# design.net
KiCad netlist of a schematic drawn in Altium Designer
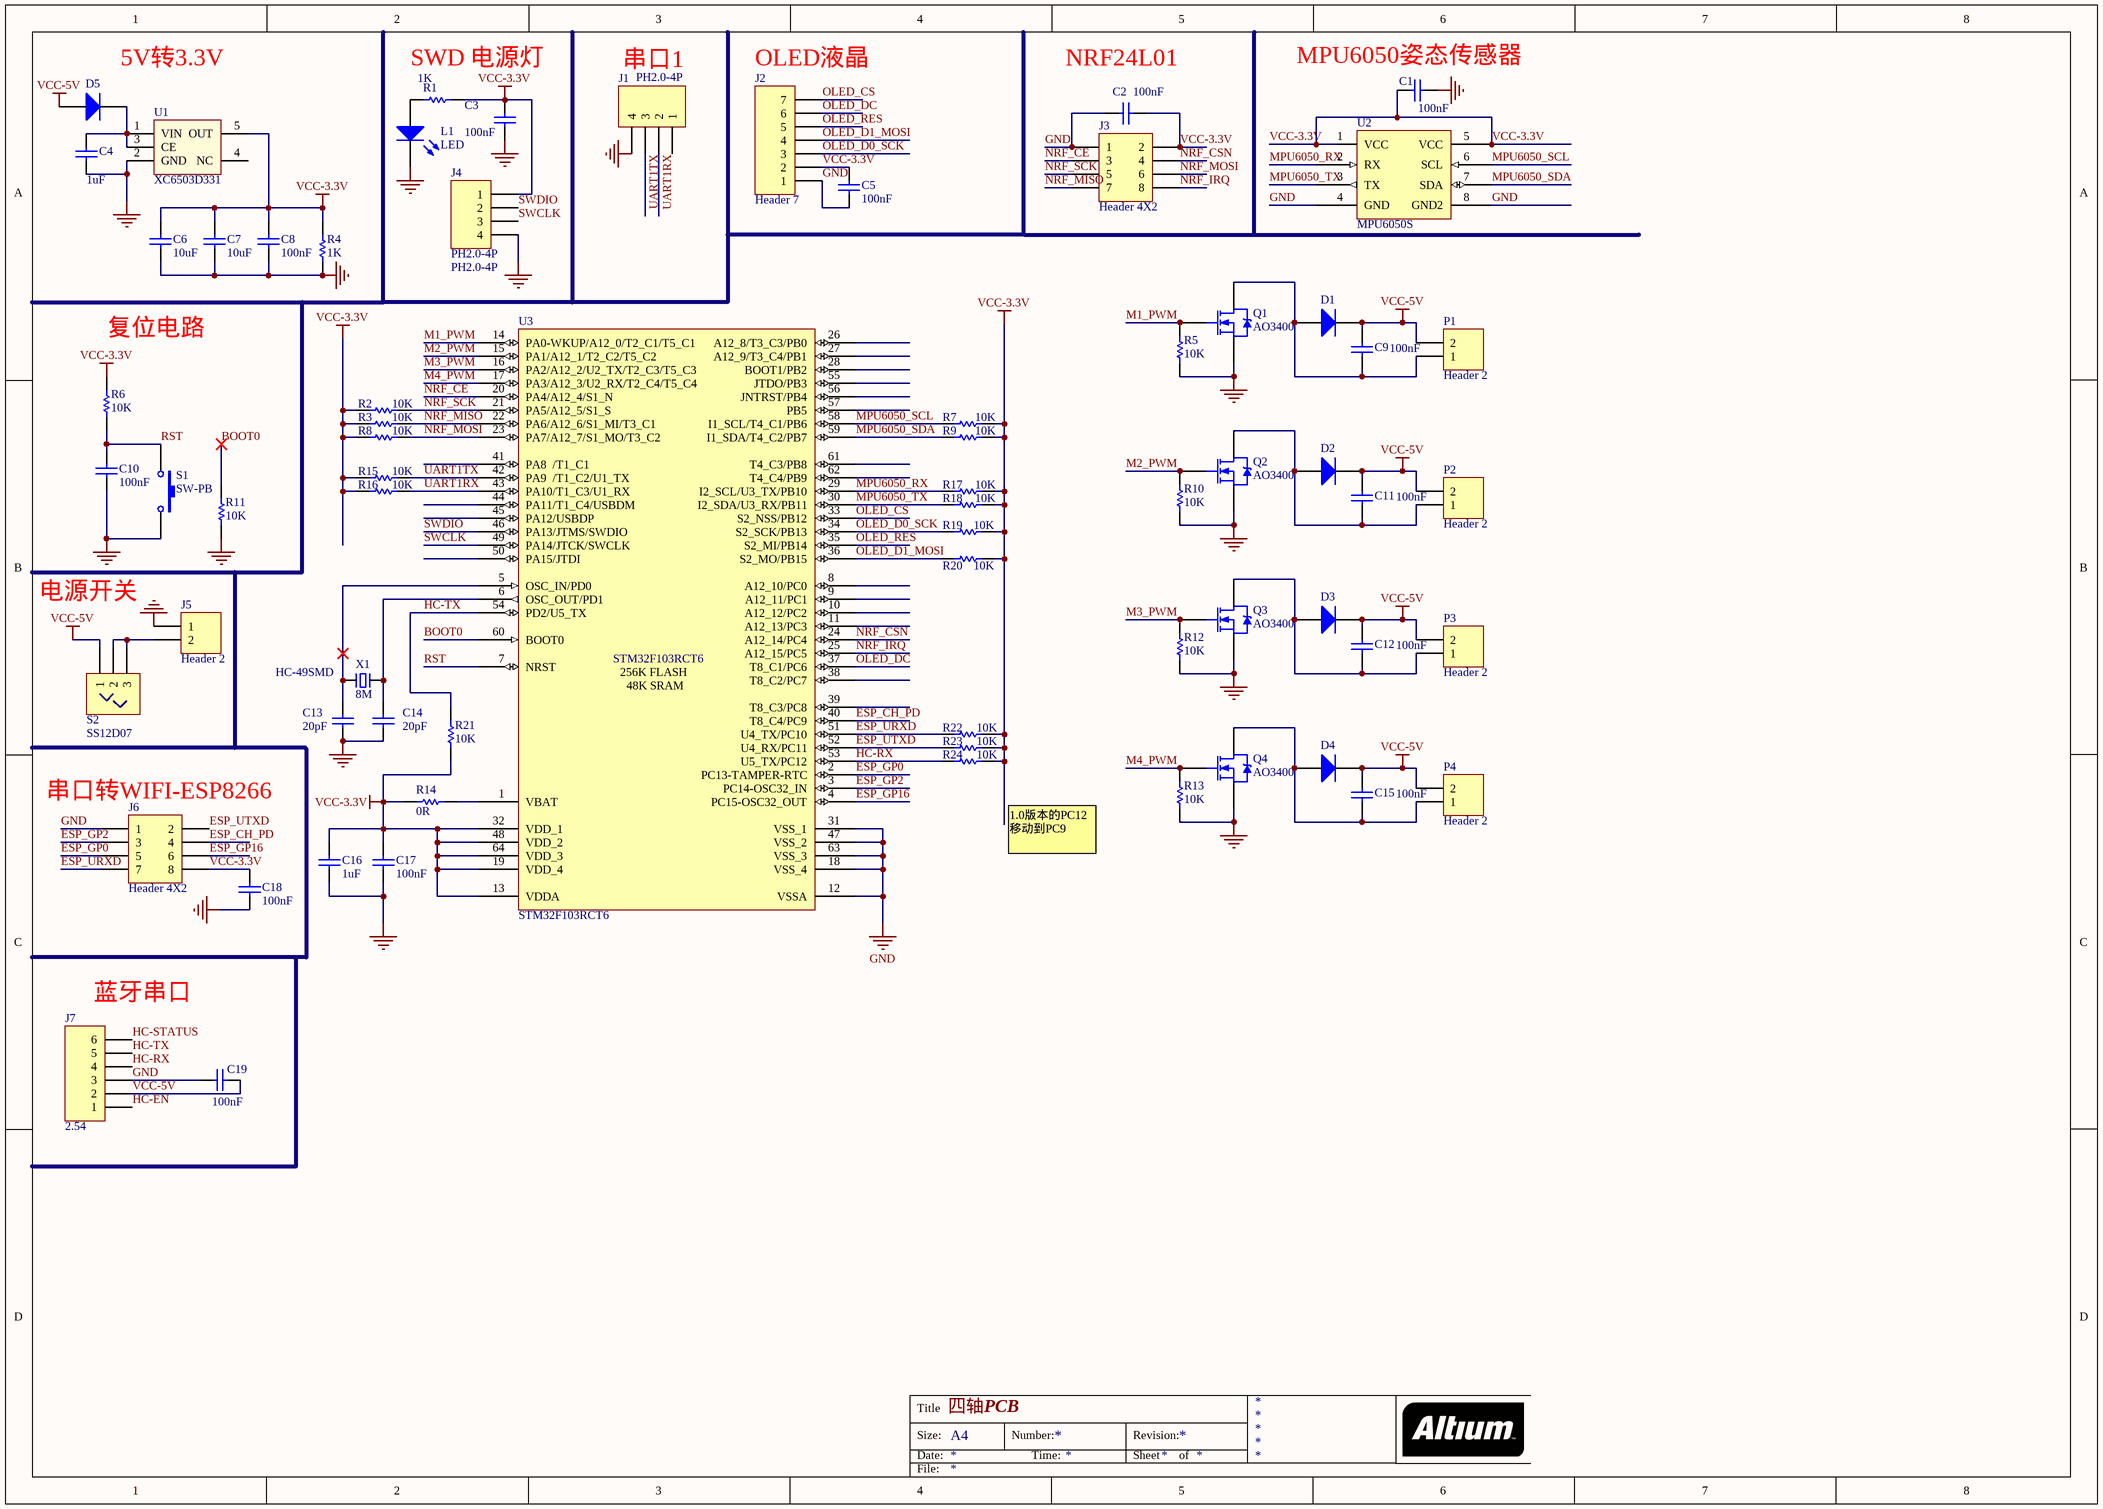
[diagram p0: 四轴.SchDoc]

(export (version "E")
  (design (tool "Eeschema 10.0.6"))
  (components
    (comp (ref "C1")
      (value "100nF")
      (footprint "LiyaoPCB库:0603")
      (description "Capacitor")
      (fields (field (name "PUBLISHER") "Altium Limited"))
      (libsource (lib "Miscellaneous Devices") (part "Cap"))
    )
    (comp (ref "C2")
      (value "100nF")
      (footprint "LiyaoPCB库:0603")
      (description "Capacitor")
      (fields (field (name "PUBLISHER") "Altium Limited"))
      (libsource (lib "Miscellaneous Devices") (part "Cap"))
    )
    (comp (ref "C3")
      (value "100nF")
      (footprint "0603")
      (description "Capacitor")
      (fields (field (name "PUBLISHER") "Altium Limited"))
      (libsource (lib "Miscellaneous Devices") (part "Cap"))
    )
    (comp (ref "C4")
      (value "1uF")
      (footprint "0603")
      (description "Capacitor")
      (fields (field (name "PUBLISHER") "Altium Limited"))
      (libsource (lib "Miscellaneous Devices") (part "Cap"))
    )
    (comp (ref "C5")
      (value "100nF")
      (footprint "LiyaoPCB库:0603")
      (description "Capacitor")
      (fields (field (name "PUBLISHER") "Altium Limited"))
      (libsource (lib "Miscellaneous Devices") (part "Cap"))
    )
    (comp (ref "C6")
      (value "10uF")
      (footprint "0603")
      (description "Capacitor")
      (fields (field (name "PUBLISHER") "Altium Limited"))
      (libsource (lib "Miscellaneous Devices") (part "Cap"))
    )
    (comp (ref "C7")
      (value "10uF")
      (footprint "0603")
      (description "Capacitor")
      (fields (field (name "PUBLISHER") "Altium Limited"))
      (libsource (lib "Miscellaneous Devices") (part "Cap"))
    )
    (comp (ref "C8")
      (value "100nF")
      (footprint "0603")
      (description "Capacitor")
      (fields (field (name "PUBLISHER") "Altium Limited"))
      (libsource (lib "Miscellaneous Devices") (part "Cap"))
    )
    (comp (ref "C9")
      (value "100nF")
      (footprint "0603")
      (description "Capacitor")
      (fields (field (name "PUBLISHER") "Altium Limited"))
      (libsource (lib "Miscellaneous Devices") (part "Cap"))
    )
    (comp (ref "C10")
      (value "100nF")
      (footprint "0603")
      (description "Capacitor")
      (fields (field (name "PUBLISHER") "Altium Limited"))
      (libsource (lib "Miscellaneous Devices") (part "Cap"))
    )
    (comp (ref "C11")
      (value "100nF")
      (footprint "0603")
      (description "Capacitor")
      (fields (field (name "PUBLISHER") "Altium Limited"))
      (libsource (lib "Miscellaneous Devices") (part "Cap"))
    )
    (comp (ref "C12")
      (value "100nF")
      (footprint "0603")
      (description "Capacitor")
      (fields (field (name "PUBLISHER") "Altium Limited"))
      (libsource (lib "Miscellaneous Devices") (part "Cap"))
    )
    (comp (ref "C13")
      (value "20pF")
      (footprint "0603")
      (description "Capacitor")
      (fields (field (name "PUBLISHER") "Altium Limited"))
      (libsource (lib "Miscellaneous Devices") (part "Cap"))
    )
    (comp (ref "C14")
      (value "20pF")
      (footprint "0603")
      (description "Capacitor")
      (fields (field (name "PUBLISHER") "Altium Limited"))
      (libsource (lib "Miscellaneous Devices") (part "Cap"))
    )
    (comp (ref "C15")
      (value "100nF")
      (footprint "0603")
      (description "Capacitor")
      (fields (field (name "PUBLISHER") "Altium Limited"))
      (libsource (lib "Miscellaneous Devices") (part "Cap"))
    )
    (comp (ref "C16")
      (value "1uF")
      (footprint "LiyaoPCB库:0603")
      (description "Capacitor")
      (fields (field (name "PUBLISHER") "Altium Limited"))
      (libsource (lib "Miscellaneous Devices") (part "Cap"))
    )
    (comp (ref "C17")
      (value "100nF")
      (footprint "LiyaoPCB库:0603")
      (description "Capacitor")
      (fields (field (name "PUBLISHER") "Altium Limited"))
      (libsource (lib "Miscellaneous Devices") (part "Cap"))
    )
    (comp (ref "C18")
      (value "100nF")
      (footprint "LiyaoPCB库:0603")
      (description "Capacitor")
      (fields (field (name "PUBLISHER") "Altium Limited"))
      (libsource (lib "Miscellaneous Devices") (part "Cap"))
    )
    (comp (ref "C19")
      (value "100nF")
      (footprint "LiyaoPCB库:0603")
      (description "Capacitor")
      (fields (field (name "PUBLISHER") "Altium Limited"))
      (libsource (lib "Miscellaneous Devices") (part "Cap"))
    )
    (comp (ref "D1")
      (value "SS14")
      (footprint "LiyaoPCB库:SMA")
      (description "28V 1A")
      (fields (field (name "PUBLISHER") "Altium Limited"))
      (libsource (lib "Liyao原理图库") (part "SS14"))
    )
    (comp (ref "D2")
      (value "SS14")
      (footprint "LiyaoPCB库:SMA")
      (description "28V 1A")
      (fields (field (name "PUBLISHER") "Altium Limited"))
      (libsource (lib "Liyao原理图库") (part "SS14"))
    )
    (comp (ref "D3")
      (value "SS14")
      (footprint "LiyaoPCB库:SMA")
      (description "28V 1A")
      (fields (field (name "PUBLISHER") "Altium Limited"))
      (libsource (lib "Liyao原理图库") (part "SS14"))
    )
    (comp (ref "D4")
      (value "SS14")
      (footprint "LiyaoPCB库:SMA")
      (description "28V 1A")
      (fields (field (name "PUBLISHER") "Altium Limited"))
      (libsource (lib "Liyao原理图库") (part "SS14"))
    )
    (comp (ref "D5")
      (value "SS14")
      (footprint "LiyaoPCB库:SMA")
      (description "28V 1A")
      (fields (field (name "PUBLISHER") "Altium Limited"))
      (libsource (lib "Liyao原理图库") (part "SS14"))
    )
    (comp (ref "J1")
      (value "PH2.0-4P")
      (footprint "PH2.0-4P")
      (description "Header, 4-Pin")
      (fields (field (name "PUBLISHER") "Altium Limited"))
      (libsource (lib "Miscellaneous Connectors") (part "Header 4"))
    )
    (comp (ref "J2")
      (value "Header 7")
      (footprint "HDR1X7")
      (description "Header, 7-Pin")
      (fields (field (name "PUBLISHER") "Altium Limited"))
      (libsource (lib "Miscellaneous Connectors") (part "Header 7"))
    )
    (comp (ref "J3")
      (value "Header 4X2")
      (footprint "HDR2X4")
      (description "Header, 4-Pin, Dual row")
      (fields (field (name "PUBLISHER") "Altium Limited"))
      (libsource (lib "Miscellaneous Connectors") (part "Header 4X2"))
    )
    (comp (ref "J4")
      (value "PH2.0-4P")
      (footprint "PH2.0-4P")
      (description "Header, 4-Pin")
      (fields (field (name "ALTIUM_VALUE") "PH2.0-4P") (field (name "PUBLISHER") "Altium Limited"))
      (libsource (lib "") (part "Header 4_1"))
    )
    (comp (ref "J5")
      (value "Header 2")
      (footprint "PH2.0-2P")
      (description "Header, 2-Pin")
      (fields (field (name "PUBLISHER") "Altium Limited"))
      (libsource (lib "Miscellaneous Connectors") (part "Header 2"))
    )
    (comp (ref "J6")
      (value "Header 4X2")
      (footprint "HDR2X4")
      (description "Header, 4-Pin, Dual row")
      (fields (field (name "PUBLISHER") "Altium Limited"))
      (libsource (lib "Miscellaneous Connectors") (part "Header 4X2"))
    )
    (comp (ref "J7")
      (value "2.54")
      (footprint "HDR1X6")
      (description "Header, 6-Pin")
      (fields (field (name "PUBLISHER") "Altium Limited"))
      (libsource (lib "Liyao端子库") (part "Header 6"))
    )
    (comp (ref "L1") (value "LED") (footprint "0603") (libsource (lib "Sparks") (part "LED")))
    (comp (ref "P1")
      (value "Header 2")
      (footprint "HDR1X2")
      (description "Header, 2-Pin")
      (fields (field (name "PUBLISHER") "Altium Limited"))
      (libsource (lib "") (part "Header 2_1"))
    )
    (comp (ref "P2")
      (value "Header 2")
      (footprint "HDR1X2")
      (description "Header, 2-Pin")
      (fields (field (name "PUBLISHER") "Altium Limited"))
      (libsource (lib "") (part "Header 2_1"))
    )
    (comp (ref "P3")
      (value "Header 2")
      (footprint "HDR1X2")
      (description "Header, 2-Pin")
      (fields (field (name "PUBLISHER") "Altium Limited"))
      (libsource (lib "") (part "Header 2_1"))
    )
    (comp (ref "P4")
      (value "Header 2")
      (footprint "HDR1X2")
      (description "Header, 2-Pin")
      (fields (field (name "PUBLISHER") "Altium Limited"))
      (libsource (lib "") (part "Header 2_1"))
    )
    (comp (ref "Q1")
      (value "AO3400")
      (footprint "SOT-23")
      (description "N-Channel MOSFET")
      (fields (field (name "PUBLISHER") "Altium Limited"))
      (libsource (lib "Liyao原理图库") (part "MOS-N"))
    )
    (comp (ref "Q2")
      (value "AO3400")
      (footprint "SOT-23")
      (description "N-Channel MOSFET")
      (fields (field (name "PUBLISHER") "Altium Limited"))
      (libsource (lib "Liyao原理图库") (part "MOS-N"))
    )
    (comp (ref "Q3")
      (value "AO3400")
      (footprint "SOT-23")
      (description "N-Channel MOSFET")
      (fields (field (name "PUBLISHER") "Altium Limited"))
      (libsource (lib "Liyao原理图库") (part "MOS-N"))
    )
    (comp (ref "Q4")
      (value "AO3400")
      (footprint "SOT-23")
      (description "N-Channel MOSFET")
      (fields (field (name "PUBLISHER") "Altium Limited"))
      (libsource (lib "Liyao原理图库") (part "MOS-N"))
    )
    (comp (ref "R1")
      (value "1K")
      (footprint "0603")
      (description "Resistor")
      (fields (field (name "PUBLISHER") "Altium Limited"))
      (libsource (lib "Miscellaneous Devices") (part "Res1"))
    )
    (comp (ref "R2")
      (value "10K")
      (footprint "C0603_M1608")
      (description "电阻0603")
      (fields (field (name "PUBLISHER") "Altium Limited"))
      (libsource (lib "Liyao原理图库") (part "Res"))
    )
    (comp (ref "R3")
      (value "10K")
      (footprint "C0603_M1608")
      (description "电阻0603")
      (fields (field (name "PUBLISHER") "Altium Limited"))
      (libsource (lib "Liyao原理图库") (part "Res"))
    )
    (comp (ref "R4")
      (value "1K")
      (footprint "0603")
      (description "Resistor")
      (fields (field (name "PUBLISHER") "Altium Limited"))
      (libsource (lib "Miscellaneous Devices") (part "Res1"))
    )
    (comp (ref "R5")
      (value "10K")
      (footprint "LiyaoPCB库:0603")
      (description "Resistor")
      (fields (field (name "PUBLISHER") "Altium Limited"))
      (libsource (lib "Miscellaneous Devices") (part "Res1"))
    )
    (comp (ref "R6")
      (value "10K")
      (footprint "0603")
      (description "Resistor")
      (fields (field (name "PUBLISHER") "Altium Limited"))
      (libsource (lib "Miscellaneous Devices") (part "Res1"))
    )
    (comp (ref "R7")
      (value "10K")
      (footprint "0603")
      (description "Resistor")
      (fields (field (name "PUBLISHER") "Altium Limited"))
      (libsource (lib "Miscellaneous Devices") (part "Res1"))
    )
    (comp (ref "R8")
      (value "10K")
      (footprint "C0603_M1608")
      (description "电阻0603")
      (fields (field (name "PUBLISHER") "Altium Limited"))
      (libsource (lib "Liyao原理图库") (part "Res"))
    )
    (comp (ref "R9")
      (value "10K")
      (footprint "0603")
      (description "Resistor")
      (fields (field (name "PUBLISHER") "Altium Limited"))
      (libsource (lib "Miscellaneous Devices") (part "Res1"))
    )
    (comp (ref "R10")
      (value "10K")
      (footprint "LiyaoPCB库:0603")
      (description "Resistor")
      (fields (field (name "PUBLISHER") "Altium Limited"))
      (libsource (lib "Miscellaneous Devices") (part "Res1"))
    )
    (comp (ref "R11")
      (value "10K")
      (footprint "0603")
      (description "Resistor")
      (fields (field (name "PUBLISHER") "Altium Limited"))
      (libsource (lib "Miscellaneous Devices") (part "Res1"))
    )
    (comp (ref "R12")
      (value "10K")
      (footprint "LiyaoPCB库:0603")
      (description "Resistor")
      (fields (field (name "PUBLISHER") "Altium Limited"))
      (libsource (lib "Miscellaneous Devices") (part "Res1"))
    )
    (comp (ref "R13")
      (value "10K")
      (footprint "LiyaoPCB库:0603")
      (description "Resistor")
      (fields (field (name "PUBLISHER") "Altium Limited"))
      (libsource (lib "Miscellaneous Devices") (part "Res1"))
    )
    (comp (ref "R14")
      (value "0R")
      (footprint "0603")
      (description "Resistor")
      (fields (field (name "PUBLISHER") "Altium Limited"))
      (libsource (lib "Miscellaneous Devices") (part "Res1"))
    )
    (comp (ref "R15")
      (value "10K")
      (footprint "C0603_M1608")
      (description "电阻0603")
      (fields (field (name "PUBLISHER") "Altium Limited"))
      (libsource (lib "Liyao原理图库") (part "Res"))
    )
    (comp (ref "R16")
      (value "10K")
      (footprint "C0603_M1608")
      (description "电阻0603")
      (fields (field (name "PUBLISHER") "Altium Limited"))
      (libsource (lib "Liyao原理图库") (part "Res"))
    )
    (comp (ref "R17")
      (value "10K")
      (footprint "C0603_M1608")
      (description "电阻0603")
      (fields (field (name "PUBLISHER") "Altium Limited"))
      (libsource (lib "Liyao原理图库") (part "Res"))
    )
    (comp (ref "R18")
      (value "10K")
      (footprint "C0603_M1608")
      (description "电阻0603")
      (fields (field (name "PUBLISHER") "Altium Limited"))
      (libsource (lib "Liyao原理图库") (part "Res"))
    )
    (comp (ref "R19")
      (value "10K")
      (footprint "C0603_M1608")
      (description "电阻0603")
      (fields (field (name "PUBLISHER") "Altium Limited"))
      (libsource (lib "Liyao原理图库") (part "Res"))
    )
    (comp (ref "R20")
      (value "10K")
      (footprint "C0603_M1608")
      (description "电阻0603")
      (fields (field (name "PUBLISHER") "Altium Limited"))
      (libsource (lib "Liyao原理图库") (part "Res"))
    )
    (comp (ref "R21")
      (value "10K")
      (footprint "C0603_M1608")
      (description "电阻0603")
      (fields (field (name "PUBLISHER") "Altium Limited"))
      (libsource (lib "Liyao原理图库") (part "Res"))
    )
    (comp (ref "R22")
      (value "10K")
      (footprint "C0603_M1608")
      (description "电阻0603")
      (fields (field (name "PUBLISHER") "Altium Limited"))
      (libsource (lib "Liyao原理图库") (part "Res"))
    )
    (comp (ref "R23")
      (value "10K")
      (footprint "C0603_M1608")
      (description "电阻0603")
      (fields (field (name "PUBLISHER") "Altium Limited"))
      (libsource (lib "Liyao原理图库") (part "Res"))
    )
    (comp (ref "R24")
      (value "10K")
      (footprint "C0603_M1608")
      (description "电阻0603")
      (fields (field (name "PUBLISHER") "Altium Limited"))
      (libsource (lib "Liyao原理图库") (part "Res"))
    )
    (comp (ref "S1")
      (value "SW-PB")
      (footprint "SW-KEY")
      (description "Switch")
      (fields (field (name "PUBLISHER") "Altium Limited"))
      (libsource (lib "Miscellaneous Devices") (part "SW-PB"))
    )
    (comp (ref "S2")
      (value "SS12D07")
      (footprint "LiyaoPCB库:SS-12D07")
      (libsource (lib "Liyao原理图库") (part "SS12D07"))
    )
    (comp (ref "U1")
      (value "XC6503D331")
      (footprint "SOT23-5")
      (libsource (lib "CYSchlib") (part "XC6503Dxxx"))
    )
    (comp (ref "U2")
      (value "MPU6050S")
      (footprint "LiyaoPCB库:MPU6050S")
      (libsource (lib "Liyao原理图库") (part "MPU6050S"))
    )
    (comp (ref "U3")
      (value "STM32F103RCT6")
      (footprint "LQFP64_N")
      (description "256K Flash 48K RAM")
      (fields (field (name "PUBLISHER") "Altium Limited"))
      (libsource (lib "Liyao原理图库") (part "STM32F103RCT6"))
    )
    (comp (ref "X1")
      (value "8M")
      (footprint "HC-49SMD")
      (fields (field (name "ALTIUM_VALUE") "HC-49SMD"))
      (libsource (lib "CYSchlib") (part "XTAL"))
    )
  )
  (nets
    (net (code "1") (name "/BOOT0") (class "Default")
      (node (ref "R11") (pin "1") (pinfunction "1_1") (pintype "passive"))
      (node (ref "U3") (pin "60") (pinfunction "BOOT0_60") (pintype "input"))
    )
    (net (code "2") (name "/ESP_CH_PD") (class "Default")
      (node (ref "J6") (pin "4") (pinfunction "4_4") (pintype "passive"))
      (node (ref "U3") (pin "40") (pinfunction "T8_C4/PC9_40") (pintype "bidirectional"))
    )
    (net (code "3") (name "/ESP_GP0") (class "Default")
      (node (ref "J6") (pin "5") (pinfunction "5_5") (pintype "passive"))
      (node (ref "U3") (pin "2") (pinfunction "PC13-TAMPER-RTC_2") (pintype "bidirectional"))
    )
    (net (code "4") (name "/ESP_GP2") (class "Default")
      (node (ref "J6") (pin "3") (pinfunction "3_3") (pintype "passive"))
      (node (ref "U3") (pin "3") (pinfunction "PC14-OSC32_IN_3") (pintype "bidirectional"))
    )
    (net (code "5") (name "/ESP_GP16") (class "Default")
      (node (ref "J6") (pin "6") (pinfunction "6_6") (pintype "passive"))
      (node (ref "U3") (pin "4") (pinfunction "PC15-OSC32_OUT_4") (pintype "bidirectional"))
    )
    (net (code "6") (name "/ESP_URXD") (class "Default")
      (node (ref "J6") (pin "7") (pinfunction "7_7") (pintype "passive"))
      (node (ref "R22") (pin "1") (pinfunction "1_1") (pintype "passive"))
      (node (ref "U3") (pin "51") (pinfunction "U4_TX/PC10_51") (pintype "bidirectional"))
    )
    (net (code "7") (name "/ESP_UTXD") (class "Default")
      (node (ref "J6") (pin "2") (pinfunction "2_2") (pintype "passive"))
      (node (ref "R23") (pin "1") (pinfunction "1_1") (pintype "passive"))
      (node (ref "U3") (pin "52") (pinfunction "U4_RX/PC11_52") (pintype "bidirectional"))
    )
    (net (code "8") (name "/HC-EN") (class "Default")
      (node (ref "J7") (pin "1") (pinfunction "1_1") (pintype "passive"))
    )
    (net (code "9") (name "/HC-RX") (class "Default")
      (node (ref "J7") (pin "4") (pinfunction "4_4") (pintype "passive"))
      (node (ref "R24") (pin "1") (pinfunction "1_1") (pintype "passive"))
      (node (ref "U3") (pin "53") (pinfunction "U5_TX/PC12_53") (pintype "bidirectional"))
    )
    (net (code "10") (name "/HC-STATUS") (class "Default")
      (node (ref "J7") (pin "6") (pinfunction "6_6") (pintype "passive"))
    )
    (net (code "11") (name "/HC-TX") (class "Default")
      (node (ref "J7") (pin "5") (pinfunction "5_5") (pintype "passive"))
      (node (ref "R21") (pin "2") (pinfunction "2_2") (pintype "passive"))
      (node (ref "U3") (pin "54") (pinfunction "PD2/U5_TX_54") (pintype "bidirectional"))
    )
    (net (code "12") (name "/M1_PWM") (class "Default")
      (node (ref "Q1") (pin "1") (pinfunction "G_1") (pintype "passive"))
      (node (ref "R5") (pin "2") (pinfunction "2_2") (pintype "passive"))
      (node (ref "U3") (pin "14") (pinfunction "PA0-WKUP/A12_0/T2_C1/T5_C1_14") (pintype "bidirectional"))
    )
    (net (code "13") (name "/M2_PWM") (class "Default")
      (node (ref "Q2") (pin "1") (pinfunction "G_1") (pintype "passive"))
      (node (ref "R10") (pin "2") (pinfunction "2_2") (pintype "passive"))
      (node (ref "U3") (pin "15") (pinfunction "PA1/A12_1/T2_C2/T5_C2_15") (pintype "bidirectional"))
    )
    (net (code "14") (name "/M3_PWM") (class "Default")
      (node (ref "Q3") (pin "1") (pinfunction "G_1") (pintype "passive"))
      (node (ref "R12") (pin "2") (pinfunction "2_2") (pintype "passive"))
      (node (ref "U3") (pin "16") (pinfunction "PA2/A12_2/U2_TX/T2_C3/T5_C3_16") (pintype "bidirectional"))
    )
    (net (code "15") (name "/M4_PWM") (class "Default")
      (node (ref "Q4") (pin "1") (pinfunction "G_1") (pintype "passive"))
      (node (ref "R13") (pin "2") (pinfunction "2_2") (pintype "passive"))
      (node (ref "U3") (pin "17") (pinfunction "PA3/A12_3/U2_RX/T2_C4/T5_C4_17") (pintype "bidirectional"))
    )
    (net (code "16") (name "/MPU6050_RX") (class "Default")
      (node (ref "R17") (pin "1") (pinfunction "1_1") (pintype "passive"))
      (node (ref "U2") (pin "2") (pinfunction "RX_2") (pintype "input"))
      (node (ref "U3") (pin "29") (pinfunction "I2_SCL/U3_TX/PB10_29") (pintype "bidirectional"))
    )
    (net (code "17") (name "/MPU6050_SCL") (class "Default")
      (node (ref "R7") (pin "2") (pinfunction "2_2") (pintype "passive"))
      (node (ref "U2") (pin "6") (pinfunction "SCL_6") (pintype "input"))
      (node (ref "U3") (pin "58") (pinfunction "I1_SCL/T4_C1/PB6_58") (pintype "bidirectional"))
    )
    (net (code "18") (name "/MPU6050_SDA") (class "Default")
      (node (ref "R9") (pin "2") (pinfunction "2_2") (pintype "passive"))
      (node (ref "U2") (pin "7") (pinfunction "SDA_7") (pintype "bidirectional"))
      (node (ref "U3") (pin "59") (pinfunction "I1_SDA/T4_C2/PB7_59") (pintype "bidirectional"))
    )
    (net (code "19") (name "/MPU6050_TX") (class "Default")
      (node (ref "R18") (pin "1") (pinfunction "1_1") (pintype "passive"))
      (node (ref "U2") (pin "3") (pinfunction "TX_3") (pintype "output"))
      (node (ref "U3") (pin "30") (pinfunction "I2_SDA/U3_RX/PB11_30") (pintype "bidirectional"))
    )
    (net (code "20") (name "/NRF_CE") (class "Default")
      (node (ref "J3") (pin "3") (pinfunction "3_3") (pintype "passive"))
      (node (ref "U3") (pin "20") (pinfunction "PA4/A12_4/S1_N_20") (pintype "bidirectional"))
    )
    (net (code "21") (name "/NRF_CSN") (class "Default")
      (node (ref "J3") (pin "4") (pinfunction "4_4") (pintype "passive"))
      (node (ref "U3") (pin "24") (pinfunction "A12_14/PC4_24") (pintype "bidirectional"))
    )
    (net (code "22") (name "/NRF_IRQ") (class "Default")
      (node (ref "J3") (pin "8") (pinfunction "8_8") (pintype "passive"))
      (node (ref "U3") (pin "25") (pinfunction "A12_15/PC5_25") (pintype "bidirectional"))
    )
    (net (code "23") (name "/NRF_MISO") (class "Default")
      (node (ref "J3") (pin "7") (pinfunction "7_7") (pintype "passive"))
      (node (ref "R3") (pin "2") (pinfunction "2_2") (pintype "passive"))
      (node (ref "U3") (pin "22") (pinfunction "PA6/A12_6/S1_MI/T3_C1_22") (pintype "bidirectional"))
    )
    (net (code "24") (name "/NRF_MOSI") (class "Default")
      (node (ref "J3") (pin "6") (pinfunction "6_6") (pintype "passive"))
      (node (ref "R8") (pin "2") (pinfunction "2_2") (pintype "passive"))
      (node (ref "U3") (pin "23") (pinfunction "PA7/A12_7/S1_MO/T3_C2_23") (pintype "bidirectional"))
    )
    (net (code "25") (name "/NRF_SCK") (class "Default")
      (node (ref "J3") (pin "5") (pinfunction "5_5") (pintype "passive"))
      (node (ref "R2") (pin "2") (pinfunction "2_2") (pintype "passive"))
      (node (ref "U3") (pin "21") (pinfunction "PA5/A12_5/S1_S_21") (pintype "bidirectional"))
    )
    (net (code "26") (name "/OLED_CS") (class "Default")
      (node (ref "J2") (pin "7") (pinfunction "7_7") (pintype "passive"))
      (node (ref "U3") (pin "33") (pinfunction "S2_NSS/PB12_33") (pintype "bidirectional"))
    )
    (net (code "27") (name "/OLED_D0_SCK") (class "Default")
      (node (ref "J2") (pin "3") (pinfunction "3_3") (pintype "passive"))
      (node (ref "R19") (pin "1") (pinfunction "1_1") (pintype "passive"))
      (node (ref "U3") (pin "34") (pinfunction "S2_SCK/PB13_34") (pintype "bidirectional"))
    )
    (net (code "28") (name "/OLED_D1_MOSI") (class "Default")
      (node (ref "J2") (pin "4") (pinfunction "4_4") (pintype "passive"))
      (node (ref "R20") (pin "1") (pinfunction "1_1") (pintype "passive"))
      (node (ref "U3") (pin "36") (pinfunction "S2_MO/PB15_36") (pintype "bidirectional"))
    )
    (net (code "29") (name "/OLED_DC") (class "Default")
      (node (ref "J2") (pin "6") (pinfunction "6_6") (pintype "passive"))
      (node (ref "U3") (pin "37") (pinfunction "T8_C1/PC6_37") (pintype "bidirectional"))
    )
    (net (code "30") (name "/OLED_RES") (class "Default")
      (node (ref "J2") (pin "5") (pinfunction "5_5") (pintype "passive"))
      (node (ref "U3") (pin "35") (pinfunction "S2_MI/PB14_35") (pintype "bidirectional"))
    )
    (net (code "31") (name "/RST") (class "Default")
      (node (ref "C10") (pin "1") (pinfunction "1_1") (pintype "passive"))
      (node (ref "R6") (pin "2") (pinfunction "2_2") (pintype "passive"))
      (node (ref "S1") (pin "1") (pinfunction "1_1") (pintype "passive"))
      (node (ref "U3") (pin "7") (pinfunction "NRST_7") (pintype "bidirectional"))
    )
    (net (code "32") (name "/SWCLK") (class "Default")
      (node (ref "J4") (pin "3") (pinfunction "3_3") (pintype "passive"))
      (node (ref "U3") (pin "49") (pinfunction "PA14/JTCK/SWCLK_49") (pintype "bidirectional"))
    )
    (net (code "33") (name "/SWDIO") (class "Default")
      (node (ref "J4") (pin "2") (pinfunction "2_2") (pintype "passive"))
      (node (ref "U3") (pin "46") (pinfunction "PA13/JTMS/SWDIO_46") (pintype "bidirectional"))
    )
    (net (code "34") (name "/UART1RX") (class "Default")
      (node (ref "J1") (pin "2") (pinfunction "2_2") (pintype "passive"))
      (node (ref "R16") (pin "2") (pinfunction "2_2") (pintype "passive"))
      (node (ref "U3") (pin "43") (pinfunction "PA10/T1_C3/U1_RX_43") (pintype "bidirectional"))
    )
    (net (code "35") (name "/UART1TX") (class "Default")
      (node (ref "J1") (pin "3") (pinfunction "3_3") (pintype "passive"))
      (node (ref "R15") (pin "2") (pinfunction "2_2") (pintype "passive"))
      (node (ref "U3") (pin "42") (pinfunction "PA9__/T1_C2/U1_TX_42") (pintype "bidirectional"))
    )
    (net (code "36") (name "GND") (class "Default")
      (node (ref "C1") (pin "2") (pinfunction "2_2") (pintype "passive"))
      (node (ref "C10") (pin "2") (pinfunction "2_2") (pintype "passive"))
      (node (ref "C13") (pin "1") (pinfunction "1_1") (pintype "passive"))
      (node (ref "C14") (pin "1") (pinfunction "1_1") (pintype "passive"))
      (node (ref "C16") (pin "1") (pinfunction "1_1") (pintype "passive"))
      (node (ref "C17") (pin "1") (pinfunction "1_1") (pintype "passive"))
      (node (ref "C18") (pin "2") (pinfunction "2_2") (pintype "passive"))
      (node (ref "C19") (pin "1") (pinfunction "1_1") (pintype "passive"))
      (node (ref "C2") (pin "2") (pinfunction "2_2") (pintype "passive"))
      (node (ref "C3") (pin "2") (pinfunction "2_2") (pintype "passive"))
      (node (ref "C4") (pin "1") (pinfunction "1_1") (pintype "passive"))
      (node (ref "C5") (pin "2") (pinfunction "2_2") (pintype "passive"))
      (node (ref "C6") (pin "2") (pinfunction "2_2") (pintype "passive"))
      (node (ref "C7") (pin "1") (pinfunction "1_1") (pintype "passive"))
      (node (ref "C8") (pin "1") (pinfunction "1_1") (pintype "passive"))
      (node (ref "J1") (pin "4") (pinfunction "4_4") (pintype "passive"))
      (node (ref "J2") (pin "1") (pinfunction "1_1") (pintype "passive"))
      (node (ref "J3") (pin "1") (pinfunction "1_1") (pintype "passive"))
      (node (ref "J4") (pin "4") (pinfunction "4_4") (pintype "passive"))
      (node (ref "J5") (pin "1") (pinfunction "1_1") (pintype "passive"))
      (node (ref "J6") (pin "1") (pinfunction "1_1") (pintype "passive"))
      (node (ref "J7") (pin "3") (pinfunction "3_3") (pintype "passive"))
      (node (ref "L1") (pin "2") (pinfunction "K_2") (pintype "passive"))
      (node (ref "Q1") (pin "2") (pinfunction "S_2") (pintype "passive"))
      (node (ref "Q2") (pin "2") (pinfunction "S_2") (pintype "passive"))
      (node (ref "Q3") (pin "2") (pinfunction "S_2") (pintype "passive"))
      (node (ref "Q4") (pin "2") (pinfunction "S_2") (pintype "passive"))
      (node (ref "R10") (pin "1") (pinfunction "1_1") (pintype "passive"))
      (node (ref "R11") (pin "2") (pinfunction "2_2") (pintype "passive"))
      (node (ref "R12") (pin "1") (pinfunction "1_1") (pintype "passive"))
      (node (ref "R13") (pin "1") (pinfunction "1_1") (pintype "passive"))
      (node (ref "R4") (pin "1") (pinfunction "1_1") (pintype "passive"))
      (node (ref "R5") (pin "1") (pinfunction "1_1") (pintype "passive"))
      (node (ref "S1") (pin "2") (pinfunction "2_2") (pintype "passive"))
      (node (ref "U1") (pin "2") (pinfunction "GND_2") (pintype "passive"))
      (node (ref "U2") (pin "4") (pinfunction "GND_4") (pintype "power_in"))
      (node (ref "U2") (pin "8") (pinfunction "GND2_8") (pintype "passive"))
      (node (ref "U3") (pin "12") (pinfunction "VSSA_12") (pintype "power_in"))
      (node (ref "U3") (pin "18") (pinfunction "VSS_4_18") (pintype "power_in"))
      (node (ref "U3") (pin "31") (pinfunction "VSS_1_31") (pintype "power_in"))
      (node (ref "U3") (pin "47") (pinfunction "VSS_2_47") (pintype "power_in"))
      (node (ref "U3") (pin "63") (pinfunction "VSS_3_63") (pintype "power_in"))
    )
    (net (code "37") (name "Net-(D1-A)") (class "Default")
      (node (ref "C9") (pin "1") (pinfunction "1_1") (pintype "passive"))
      (node (ref "D1") (pin "1") (pinfunction "A_1") (pintype "passive"))
      (node (ref "P1") (pin "1") (pinfunction "1_1") (pintype "passive"))
      (node (ref "Q1") (pin "3") (pinfunction "D_3") (pintype "passive"))
    )
    (net (code "38") (name "Net-(D2-A)") (class "Default")
      (node (ref "C11") (pin "1") (pinfunction "1_1") (pintype "passive"))
      (node (ref "D2") (pin "1") (pinfunction "A_1") (pintype "passive"))
      (node (ref "P2") (pin "1") (pinfunction "1_1") (pintype "passive"))
      (node (ref "Q2") (pin "3") (pinfunction "D_3") (pintype "passive"))
    )
    (net (code "39") (name "Net-(D3-A)") (class "Default")
      (node (ref "C12") (pin "1") (pinfunction "1_1") (pintype "passive"))
      (node (ref "D3") (pin "1") (pinfunction "A_1") (pintype "passive"))
      (node (ref "P3") (pin "1") (pinfunction "1_1") (pintype "passive"))
      (node (ref "Q3") (pin "3") (pinfunction "D_3") (pintype "passive"))
    )
    (net (code "40") (name "Net-(D4-A)") (class "Default")
      (node (ref "C15") (pin "1") (pinfunction "1_1") (pintype "passive"))
      (node (ref "D4") (pin "1") (pinfunction "A_1") (pintype "passive"))
      (node (ref "P4") (pin "1") (pinfunction "1_1") (pintype "passive"))
      (node (ref "Q4") (pin "3") (pinfunction "D_3") (pintype "passive"))
    )
    (net (code "41") (name "Net-(D5-K)") (class "Default")
      (node (ref "C4") (pin "2") (pinfunction "2_2") (pintype "passive"))
      (node (ref "D5") (pin "2") (pinfunction "K_2") (pintype "passive"))
      (node (ref "U1") (pin "1") (pinfunction "VIN_1") (pintype "passive"))
      (node (ref "U1") (pin "3") (pinfunction "CE_3") (pintype "passive"))
    )
    (net (code "42") (name "Net-(J5-Pad2)") (class "Default")
      (node (ref "J5") (pin "2") (pinfunction "2_2") (pintype "passive"))
      (node (ref "S2") (pin "2") (pinfunction "2_2") (pintype "passive"))
      (node (ref "S2") (pin "3") (pinfunction "3_3") (pintype "passive"))
    )
    (net (code "43") (name "Net-(L1-A)") (class "Default")
      (node (ref "L1") (pin "1") (pinfunction "A_1") (pintype "passive"))
      (node (ref "R1") (pin "1") (pinfunction "1_1") (pintype "passive"))
    )
    (net (code "44") (name "Net-(U3-OSC_IN{slash}PD0)") (class "Default")
      (node (ref "C13") (pin "2") (pinfunction "2_2") (pintype "passive"))
      (node (ref "U3") (pin "5") (pinfunction "OSC_IN/PD0_5") (pintype "input"))
      (node (ref "X1") (pin "2") (pinfunction "2_2") (pintype "passive"))
    )
    (net (code "45") (name "Net-(U3-OSC_OUT{slash}PD1)") (class "Default")
      (node (ref "C14") (pin "2") (pinfunction "2_2") (pintype "passive"))
      (node (ref "U3") (pin "6") (pinfunction "OSC_OUT/PD1_6") (pintype "output"))
      (node (ref "X1") (pin "1") (pinfunction "1_1") (pintype "passive"))
    )
    (net (code "46") (name "Net-(U3-VBAT)") (class "Default")
      (node (ref "R14") (pin "2") (pinfunction "2_2") (pintype "passive"))
      (node (ref "U3") (pin "1") (pinfunction "VBAT_1") (pintype "power_in"))
    )
    (net (code "47") (name "VCC-3.3V") (class "Default")
      (node (ref "C1") (pin "1") (pinfunction "1_1") (pintype "passive"))
      (node (ref "C16") (pin "2") (pinfunction "2_2") (pintype "passive"))
      (node (ref "C17") (pin "2") (pinfunction "2_2") (pintype "passive"))
      (node (ref "C18") (pin "1") (pinfunction "1_1") (pintype "passive"))
      (node (ref "C2") (pin "1") (pinfunction "1_1") (pintype "passive"))
      (node (ref "C3") (pin "1") (pinfunction "1_1") (pintype "passive"))
      (node (ref "C5") (pin "1") (pinfunction "1_1") (pintype "passive"))
      (node (ref "C6") (pin "1") (pinfunction "1_1") (pintype "passive"))
      (node (ref "C7") (pin "2") (pinfunction "2_2") (pintype "passive"))
      (node (ref "C8") (pin "2") (pinfunction "2_2") (pintype "passive"))
      (node (ref "J2") (pin "2") (pinfunction "2_2") (pintype "passive"))
      (node (ref "J3") (pin "2") (pinfunction "2_2") (pintype "passive"))
      (node (ref "J4") (pin "1") (pinfunction "1_1") (pintype "passive"))
      (node (ref "J6") (pin "8") (pinfunction "8_8") (pintype "passive"))
      (node (ref "R1") (pin "2") (pinfunction "2_2") (pintype "passive"))
      (node (ref "R14") (pin "1") (pinfunction "1_1") (pintype "passive"))
      (node (ref "R15") (pin "1") (pinfunction "1_1") (pintype "passive"))
      (node (ref "R16") (pin "1") (pinfunction "1_1") (pintype "passive"))
      (node (ref "R17") (pin "2") (pinfunction "2_2") (pintype "passive"))
      (node (ref "R18") (pin "2") (pinfunction "2_2") (pintype "passive"))
      (node (ref "R19") (pin "2") (pinfunction "2_2") (pintype "passive"))
      (node (ref "R2") (pin "1") (pinfunction "1_1") (pintype "passive"))
      (node (ref "R20") (pin "2") (pinfunction "2_2") (pintype "passive"))
      (node (ref "R21") (pin "1") (pinfunction "1_1") (pintype "passive"))
      (node (ref "R22") (pin "2") (pinfunction "2_2") (pintype "passive"))
      (node (ref "R23") (pin "2") (pinfunction "2_2") (pintype "passive"))
      (node (ref "R24") (pin "2") (pinfunction "2_2") (pintype "passive"))
      (node (ref "R3") (pin "1") (pinfunction "1_1") (pintype "passive"))
      (node (ref "R4") (pin "2") (pinfunction "2_2") (pintype "passive"))
      (node (ref "R6") (pin "1") (pinfunction "1_1") (pintype "passive"))
      (node (ref "R7") (pin "1") (pinfunction "1_1") (pintype "passive"))
      (node (ref "R8") (pin "1") (pinfunction "1_1") (pintype "passive"))
      (node (ref "R9") (pin "1") (pinfunction "1_1") (pintype "passive"))
      (node (ref "U1") (pin "5") (pinfunction "OUT_5") (pintype "passive"))
      (node (ref "U2") (pin "1") (pinfunction "VCC_1") (pintype "power_in"))
      (node (ref "U2") (pin "5") (pinfunction "VCC_5") (pintype "power_in"))
      (node (ref "U3") (pin "13") (pinfunction "VDDA_13") (pintype "power_in"))
      (node (ref "U3") (pin "19") (pinfunction "VDD_4_19") (pintype "power_in"))
      (node (ref "U3") (pin "32") (pinfunction "VDD_1_32") (pintype "power_in"))
      (node (ref "U3") (pin "48") (pinfunction "VDD_2_48") (pintype "power_in"))
      (node (ref "U3") (pin "64") (pinfunction "VDD_3_64") (pintype "power_in"))
    )
    (net (code "48") (name "VCC-5V") (class "Default")
      (node (ref "C11") (pin "2") (pinfunction "2_2") (pintype "passive"))
      (node (ref "C12") (pin "2") (pinfunction "2_2") (pintype "passive"))
      (node (ref "C15") (pin "2") (pinfunction "2_2") (pintype "passive"))
      (node (ref "C19") (pin "2") (pinfunction "2_2") (pintype "passive"))
      (node (ref "C9") (pin "2") (pinfunction "2_2") (pintype "passive"))
      (node (ref "D1") (pin "2") (pinfunction "K_2") (pintype "passive"))
      (node (ref "D2") (pin "2") (pinfunction "K_2") (pintype "passive"))
      (node (ref "D3") (pin "2") (pinfunction "K_2") (pintype "passive"))
      (node (ref "D4") (pin "2") (pinfunction "K_2") (pintype "passive"))
      (node (ref "D5") (pin "1") (pinfunction "A_1") (pintype "passive"))
      (node (ref "J7") (pin "2") (pinfunction "2_2") (pintype "passive"))
      (node (ref "P1") (pin "2") (pinfunction "2_2") (pintype "passive"))
      (node (ref "P2") (pin "2") (pinfunction "2_2") (pintype "passive"))
      (node (ref "P3") (pin "2") (pinfunction "2_2") (pintype "passive"))
      (node (ref "P4") (pin "2") (pinfunction "2_2") (pintype "passive"))
      (node (ref "S2") (pin "1") (pinfunction "1_1") (pintype "passive"))
    )
    (net (code "49") (name "unconnected-(J1-Pad1)") (class "Default")
      (node (ref "J1") (pin "1") (pinfunction "1_1") (pintype "passive"))
    )
    (net (code "50") (name "unconnected-(U1-NC-Pad4)") (class "Default")
      (node (ref "U1") (pin "4") (pinfunction "NC_4") (pintype "passive"))
    )
    (net (code "51") (name "unconnected-(U3-A12_8{slash}T3_C3{slash}PB0-Pad26)") (class "Default")
      (node (ref "U3") (pin "26") (pinfunction "A12_8/T3_C3/PB0_26") (pintype "bidirectional"))
    )
    (net (code "52") (name "unconnected-(U3-A12_9{slash}T3_C4{slash}PB1-Pad27)") (class "Default")
      (node (ref "U3") (pin "27") (pinfunction "A12_9/T3_C4/PB1_27") (pintype "bidirectional"))
    )
    (net (code "53") (name "unconnected-(U3-A12_10{slash}PC0-Pad8)") (class "Default")
      (node (ref "U3") (pin "8") (pinfunction "A12_10/PC0_8") (pintype "bidirectional"))
    )
    (net (code "54") (name "unconnected-(U3-A12_11{slash}PC1-Pad9)") (class "Default")
      (node (ref "U3") (pin "9") (pinfunction "A12_11/PC1_9") (pintype "bidirectional"))
    )
    (net (code "55") (name "unconnected-(U3-A12_12{slash}PC2-Pad10)") (class "Default")
      (node (ref "U3") (pin "10") (pinfunction "A12_12/PC2_10") (pintype "bidirectional"))
    )
    (net (code "56") (name "unconnected-(U3-A12_13{slash}PC3-Pad11)") (class "Default")
      (node (ref "U3") (pin "11") (pinfunction "A12_13/PC3_11") (pintype "bidirectional"))
    )
    (net (code "57") (name "unconnected-(U3-BOOT1{slash}PB2-Pad28)") (class "Default")
      (node (ref "U3") (pin "28") (pinfunction "BOOT1/PB2_28") (pintype "bidirectional"))
    )
    (net (code "58") (name "unconnected-(U3-JNTRST{slash}PB4-Pad56)") (class "Default")
      (node (ref "U3") (pin "56") (pinfunction "JNTRST/PB4_56") (pintype "bidirectional"))
    )
    (net (code "59") (name "unconnected-(U3-JTDO{slash}PB3-Pad55)") (class "Default")
      (node (ref "U3") (pin "55") (pinfunction "JTDO/PB3_55") (pintype "bidirectional"))
    )
    (net (code "60") (name "unconnected-(U3-PA8__{slash}T1_C1-Pad41)") (class "Default")
      (node (ref "U3") (pin "41") (pinfunction "PA8__/T1_C1_41") (pintype "bidirectional"))
    )
    (net (code "61") (name "unconnected-(U3-PA11{slash}T1_C4{slash}USBDM-Pad44)") (class "Default")
      (node (ref "U3") (pin "44") (pinfunction "PA11/T1_C4/USBDM_44") (pintype "bidirectional"))
    )
    (net (code "62") (name "unconnected-(U3-PA12{slash}USBDP-Pad45)") (class "Default")
      (node (ref "U3") (pin "45") (pinfunction "PA12/USBDP_45") (pintype "bidirectional"))
    )
    (net (code "63") (name "unconnected-(U3-PA15{slash}JTDI-Pad50)") (class "Default")
      (node (ref "U3") (pin "50") (pinfunction "PA15/JTDI_50") (pintype "bidirectional"))
    )
    (net (code "64") (name "unconnected-(U3-PB5-Pad57)") (class "Default")
      (node (ref "U3") (pin "57") (pinfunction "PB5_57") (pintype "bidirectional"))
    )
    (net (code "65") (name "unconnected-(U3-T4_C3{slash}PB8-Pad61)") (class "Default")
      (node (ref "U3") (pin "61") (pinfunction "T4_C3/PB8_61") (pintype "bidirectional"))
    )
    (net (code "66") (name "unconnected-(U3-T4_C4{slash}PB9-Pad62)") (class "Default")
      (node (ref "U3") (pin "62") (pinfunction "T4_C4/PB9_62") (pintype "bidirectional"))
    )
    (net (code "67") (name "unconnected-(U3-T8_C2{slash}PC7-Pad38)") (class "Default")
      (node (ref "U3") (pin "38") (pinfunction "T8_C2/PC7_38") (pintype "bidirectional"))
    )
    (net (code "68") (name "unconnected-(U3-T8_C3{slash}PC8-Pad39)") (class "Default")
      (node (ref "U3") (pin "39") (pinfunction "T8_C3/PC8_39") (pintype "bidirectional"))
    )
  )
)
